# ADC.net
KiCad netlist of a schematic drawn in Altium Designer
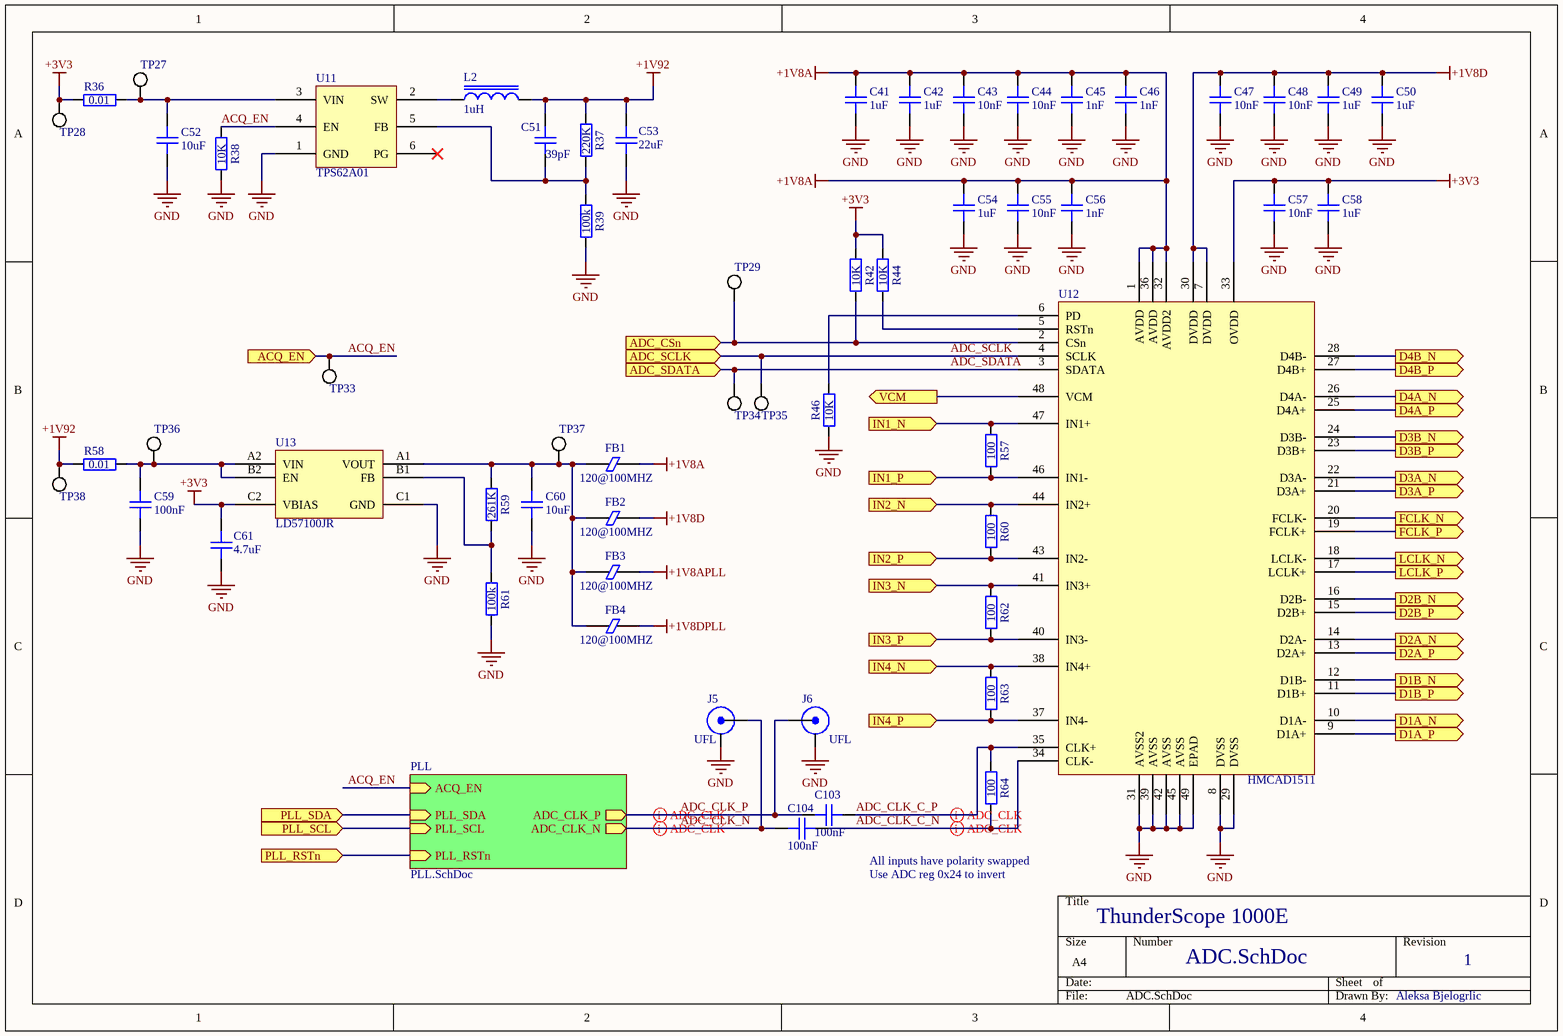
[diagram p0: ADC.SchDoc]

(export (version "E")
  (design (tool "Eeschema 10.0.6"))
  (components
    (comp (ref "C41")
      (value "1uF")
      (footprint "GEN_C_0402")
      (libsource (lib "DSO") (part "CAP 1uF 25V X5R 0402"))
    )
    (comp (ref "C42")
      (value "1uF")
      (footprint "GEN_C_0402")
      (libsource (lib "DSO") (part "CAP 1uF 25V X5R 0402"))
    )
    (comp (ref "C43")
      (value "10nF")
      (footprint "GEN_C_0402")
      (libsource (lib "DSO") (part "CAP 10nF 50V X7R 0402"))
    )
    (comp (ref "C44")
      (value "10nF")
      (footprint "GEN_C_0402")
      (libsource (lib "DSO") (part "CAP 10nF 50V X7R 0402"))
    )
    (comp (ref "C45")
      (value "1nF")
      (footprint "GEN_C_0402")
      (libsource (lib "DSO") (part "CAP 1nF 50V C0G 0402"))
    )
    (comp (ref "C46")
      (value "1nF")
      (footprint "GEN_C_0402")
      (libsource (lib "DSO") (part "CAP 1nF 50V C0G 0402"))
    )
    (comp (ref "C47")
      (value "10nF")
      (footprint "GEN_C_0402")
      (libsource (lib "DSO") (part "CAP 10nF 50V X7R 0402"))
    )
    (comp (ref "C48")
      (value "10nF")
      (footprint "GEN_C_0402")
      (libsource (lib "DSO") (part "CAP 10nF 50V X7R 0402"))
    )
    (comp (ref "C49")
      (value "1uF")
      (footprint "GEN_C_0402")
      (libsource (lib "DSO") (part "CAP 1uF 25V X5R 0402"))
    )
    (comp (ref "C50")
      (value "1uF")
      (footprint "GEN_C_0402")
      (libsource (lib "DSO") (part "CAP 1uF 25V X5R 0402"))
    )
    (comp (ref "C51")
      (value "39pF")
      (footprint "GEN_C_0402")
      (libsource (lib "DSO") (part "CAP 39pF 50V C0G 0402"))
    )
    (comp (ref "C52")
      (value "10uF")
      (footprint "GEN_C_0603")
      (libsource (lib "DSO") (part "CAP 10uF 10V X5R 0603"))
    )
    (comp (ref "C53")
      (value "22uF")
      (footprint "GEN_C_0805")
      (libsource (lib "DSO") (part "CAP 22uF 25V X5R 0805"))
    )
    (comp (ref "C54")
      (value "1uF")
      (footprint "GEN_C_0402")
      (libsource (lib "DSO") (part "CAP 1uF 25V X5R 0402"))
    )
    (comp (ref "C55")
      (value "10nF")
      (footprint "GEN_C_0402")
      (libsource (lib "DSO") (part "CAP 10nF 50V X7R 0402"))
    )
    (comp (ref "C56")
      (value "1nF")
      (footprint "GEN_C_0402")
      (libsource (lib "DSO") (part "CAP 1nF 50V C0G 0402"))
    )
    (comp (ref "C57")
      (value "10nF")
      (footprint "GEN_C_0402")
      (libsource (lib "DSO") (part "CAP 10nF 50V X7R 0402"))
    )
    (comp (ref "C58")
      (value "1uF")
      (footprint "GEN_C_0402")
      (libsource (lib "DSO") (part "CAP 1uF 25V X5R 0402"))
    )
    (comp (ref "C59")
      (value "100nF")
      (footprint "GEN_C_0402")
      (libsource (lib "DSO") (part "CAP 100nF 16V X7R 0402"))
    )
    (comp (ref "C60")
      (value "10uF")
      (footprint "GEN_C_0603")
      (libsource (lib "DSO") (part "CAP 10uF 10V X5R 0603"))
    )
    (comp (ref "C61")
      (value "4.7uF")
      (footprint "GEN_C_0402")
      (libsource (lib "DSO") (part "CAP 4.7uF 6.3V X5R 0402"))
    )
    (comp (ref "C103")
      (value "100nF")
      (footprint "GEN_C_0402")
      (libsource (lib "DSO") (part "CAP 100nF 16V X7R 0402"))
    )
    (comp (ref "C104")
      (value "100nF")
      (footprint "GEN_C_0402")
      (libsource (lib "DSO") (part "CAP 100nF 16V X7R 0402"))
    )
    (comp (ref "FB1")
      (value "120@100MHZ")
      (footprint "GEN_R_0402")
      (libsource (lib "DSO") (part "FERRITE BEAD 120 OHM 0402"))
    )
    (comp (ref "FB2")
      (value "120@100MHZ")
      (footprint "GEN_R_0402")
      (libsource (lib "DSO") (part "FERRITE BEAD 120 OHM 0402"))
    )
    (comp (ref "FB3")
      (value "120@100MHZ")
      (footprint "GEN_R_0402")
      (libsource (lib "DSO") (part "FERRITE BEAD 120 OHM 0402"))
    )
    (comp (ref "FB4")
      (value "120@100MHZ")
      (footprint "GEN_R_0402")
      (libsource (lib "DSO") (part "FERRITE BEAD 120 OHM 0402"))
    )
    (comp (ref "J5") (value "UFL") (footprint "TE_2334884-1") (libsource (lib "DSO") (part "UFL Jack SMD")))
    (comp (ref "J6") (value "UFL") (footprint "TE_2334884-1") (libsource (lib "DSO") (part "UFL Jack SMD")))
    (comp (ref "L2")
      (value "1uH")
      (footprint "GEN_L_1210")
      (libsource (lib "DSO") (part "IND 1uH 3.1A 45 MOHM 1210"))
    )
    (comp (ref "R36")
      (value "0.01")
      (footprint "GEN_R_0603")
      (fields (field (name "TOLERANCE") "1%"))
      (libsource (lib "DSO") (part "RES 0.01 OHM 1% 1/4W 0603"))
    )
    (comp (ref "R37")
      (value "220K")
      (footprint "GEN_R_0402")
      (fields (field (name "TOLERANCE") "1%"))
      (libsource (lib "DSO") (part "RES 220K OHM 1% 1/16W 0402"))
    )
    (comp (ref "R38")
      (value "10K")
      (footprint "GEN_R_0402")
      (fields (field (name "TOLERANCE") "1%"))
      (libsource (lib "DSO") (part "RES 10K OHM 1% 1/10W 0402"))
    )
    (comp (ref "R39")
      (value "100k")
      (footprint "GEN_R_0402")
      (fields (field (name "TOLERANCE") "1%"))
      (libsource (lib "DSO") (part "RES 100K OHM 1% 1/10W 0402"))
    )
    (comp (ref "R42")
      (value "10K")
      (footprint "GEN_R_0402")
      (fields (field (name "TOLERANCE") "1%"))
      (libsource (lib "DSO") (part "RES 10K OHM 1% 1/10W 0402"))
    )
    (comp (ref "R44")
      (value "10K")
      (footprint "GEN_R_0402")
      (fields (field (name "TOLERANCE") "1%"))
      (libsource (lib "DSO") (part "RES 10K OHM 1% 1/10W 0402"))
    )
    (comp (ref "R46")
      (value "10K")
      (footprint "GEN_R_0402")
      (fields (field (name "TOLERANCE") "1%"))
      (libsource (lib "") (part "RES 10K OHM 1% 1/10W 0402_1"))
    )
    (comp (ref "R57")
      (value "100")
      (footprint "GEN_R_0402")
      (fields (field (name "TOLERANCE") "1%"))
      (libsource (lib "DSO") (part "RES 100 OHM 1% 1/10W 0402"))
    )
    (comp (ref "R58")
      (value "0.01")
      (footprint "GEN_R_0603")
      (fields (field (name "TOLERANCE") "1%"))
      (libsource (lib "DSO") (part "RES 0.01 OHM 1% 1/4W 0603"))
    )
    (comp (ref "R59")
      (value "261K")
      (footprint "GEN_R_0402")
      (fields (field (name "TOLERANCE") "1%"))
      (libsource (lib "DSO") (part "RES 261K OHM 1% 1/16W 0402"))
    )
    (comp (ref "R60")
      (value "100")
      (footprint "GEN_R_0402")
      (fields (field (name "TOLERANCE") "1%"))
      (libsource (lib "DSO") (part "RES 100 OHM 1% 1/10W 0402"))
    )
    (comp (ref "R61")
      (value "100k")
      (footprint "GEN_R_0402")
      (fields (field (name "TOLERANCE") "1%"))
      (libsource (lib "DSO") (part "RES 100K OHM 1% 1/10W 0402"))
    )
    (comp (ref "R62")
      (value "100")
      (footprint "GEN_R_0402")
      (fields (field (name "TOLERANCE") "1%"))
      (libsource (lib "DSO") (part "RES 100 OHM 1% 1/10W 0402"))
    )
    (comp (ref "R63")
      (value "100")
      (footprint "GEN_R_0402")
      (fields (field (name "TOLERANCE") "1%"))
      (libsource (lib "DSO") (part "RES 100 OHM 1% 1/10W 0402"))
    )
    (comp (ref "R64")
      (value "100")
      (footprint "GEN_R_0402")
      (fields (field (name "TOLERANCE") "1%"))
      (libsource (lib "DSO") (part "RES 100 OHM 1% 1/10W 0402"))
    )
    (comp (ref "TP27") (value "PCB") (footprint "GEN_TP_PCB") (libsource (lib "DSO") (part "TP PCB 1mm")))
    (comp (ref "TP28") (value "PCB") (footprint "GEN_TP_PCB") (libsource (lib "DSO") (part "TP PCB 1mm")))
    (comp (ref "TP29") (value "PCB") (footprint "GEN_TP_PCB") (libsource (lib "DSO") (part "TP PCB 1mm")))
    (comp (ref "TP33") (value "PCB") (footprint "GEN_TP_PCB") (libsource (lib "DSO") (part "TP PCB 1mm")))
    (comp (ref "TP34") (value "PCB") (footprint "GEN_TP_PCB") (libsource (lib "DSO") (part "TP PCB 1mm")))
    (comp (ref "TP35") (value "PCB") (footprint "GEN_TP_PCB") (libsource (lib "DSO") (part "TP PCB 1mm")))
    (comp (ref "TP36") (value "PCB") (footprint "GEN_TP_PCB") (libsource (lib "DSO") (part "TP PCB 1mm")))
    (comp (ref "TP37") (value "PCB") (footprint "GEN_TP_PCB") (libsource (lib "DSO") (part "TP PCB 1mm")))
    (comp (ref "TP38") (value "PCB") (footprint "GEN_TP_PCB") (libsource (lib "DSO") (part "TP PCB 1mm")))
    (comp (ref "U11")
      (value "TPS62A01")
      (footprint "TI_SOT563_DRL0006A")
      (libsource (lib "DSO") (part "IC BUCK TPS62A01"))
    )
    (comp (ref "U12")
      (value "HMCAD1511")
      (footprint "AD_QFN48_LP7")
      (libsource (lib "DSO") (part "IC ADC HMCAD1511"))
    )
    (comp (ref "U13")
      (value "LD57100JR")
      (footprint "ST_FlipChip6")
      (libsource (lib "DSO") (part "IC LDO LD57100JR"))
    )
  )
  (nets
    (net (code "1") (name "+1V8A") (class "Default")
      (node (ref "C41") (pin "2") (pinfunction "2_2") (pintype "passive"))
      (node (ref "C42") (pin "2") (pinfunction "2_2") (pintype "passive"))
      (node (ref "C43") (pin "2") (pinfunction "2_2") (pintype "passive"))
      (node (ref "C44") (pin "2") (pinfunction "2_2") (pintype "passive"))
      (node (ref "C45") (pin "2") (pinfunction "2_2") (pintype "passive"))
      (node (ref "C46") (pin "2") (pinfunction "2_2") (pintype "passive"))
      (node (ref "C54") (pin "2") (pinfunction "2_2") (pintype "passive"))
      (node (ref "C55") (pin "2") (pinfunction "2_2") (pintype "passive"))
      (node (ref "C56") (pin "2") (pinfunction "2_2") (pintype "passive"))
      (node (ref "FB1") (pin "2") (pinfunction "2_2") (pintype "passive"))
      (node (ref "U12") (pin "1") (pinfunction "AVDD_1") (pintype "passive"))
      (node (ref "U12") (pin "32") (pinfunction "AVDD2_32") (pintype "passive"))
      (node (ref "U12") (pin "36") (pinfunction "AVDD_36") (pintype "passive"))
    )
    (net (code "2") (name "+1V8APLL") (class "Default")
      (node (ref "FB3") (pin "2") (pinfunction "2_2") (pintype "passive"))
    )
    (net (code "3") (name "+1V8D") (class "Default")
      (node (ref "C47") (pin "2") (pinfunction "2_2") (pintype "passive"))
      (node (ref "C48") (pin "2") (pinfunction "2_2") (pintype "passive"))
      (node (ref "C49") (pin "2") (pinfunction "2_2") (pintype "passive"))
      (node (ref "C50") (pin "2") (pinfunction "2_2") (pintype "passive"))
      (node (ref "FB2") (pin "2") (pinfunction "2_2") (pintype "passive"))
      (node (ref "U12") (pin "30") (pinfunction "DVDD_30") (pintype "passive"))
      (node (ref "U12") (pin "7") (pinfunction "DVDD_7") (pintype "passive"))
    )
    (net (code "4") (name "+1V8DPLL") (class "Default")
      (node (ref "FB4") (pin "2") (pinfunction "2_2") (pintype "passive"))
    )
    (net (code "5") (name "+1V92") (class "Default")
      (node (ref "C51") (pin "2") (pinfunction "2_2") (pintype "passive"))
      (node (ref "C53") (pin "2") (pinfunction "2_2") (pintype "passive"))
      (node (ref "L2") (pin "2") (pinfunction "2_2") (pintype "passive"))
      (node (ref "R37") (pin "2") (pinfunction "2_2") (pintype "passive"))
      (node (ref "R58") (pin "1") (pinfunction "1_1") (pintype "passive"))
      (node (ref "TP38") (pin "1") (pinfunction "1_1") (pintype "passive"))
    )
    (net (code "6") (name "+3V3") (class "Default")
      (node (ref "C57") (pin "2") (pinfunction "2_2") (pintype "passive"))
      (node (ref "C58") (pin "2") (pinfunction "2_2") (pintype "passive"))
      (node (ref "C61") (pin "2") (pinfunction "2_2") (pintype "passive"))
      (node (ref "R36") (pin "1") (pinfunction "1_1") (pintype "passive"))
      (node (ref "R42") (pin "2") (pinfunction "2_2") (pintype "passive"))
      (node (ref "R44") (pin "2") (pinfunction "2_2") (pintype "passive"))
      (node (ref "TP28") (pin "1") (pinfunction "1_1") (pintype "passive"))
      (node (ref "U12") (pin "33") (pinfunction "OVDD_33") (pintype "passive"))
      (node (ref "U13") (pin "C2") (pinfunction "VBIAS_C2") (pintype "passive"))
    )
    (net (code "7") (name "/ACQ_EN") (class "Default")
      (node (ref "R38") (pin "2") (pinfunction "2_2") (pintype "passive"))
      (node (ref "TP33") (pin "1") (pinfunction "1_1") (pintype "passive"))
      (node (ref "U11") (pin "4") (pinfunction "EN_4") (pintype "passive"))
    )
    (net (code "8") (name "/ADC_CLK_C_N") (class "Default")
      (node (ref "C104") (pin "1") (pinfunction "1_1") (pintype "passive"))
      (node (ref "R64") (pin "1") (pinfunction "1_1") (pintype "passive"))
      (node (ref "U12") (pin "34") (pinfunction "CLK-_34") (pintype "passive"))
    )
    (net (code "9") (name "/ADC_CLK_C_P") (class "Default")
      (node (ref "C103") (pin "1") (pinfunction "1_1") (pintype "passive"))
      (node (ref "R64") (pin "2") (pinfunction "2_2") (pintype "passive"))
      (node (ref "U12") (pin "35") (pinfunction "CLK+_35") (pintype "passive"))
    )
    (net (code "10") (name "/ADC_CLK_N") (class "Default")
      (node (ref "C104") (pin "2") (pinfunction "2_2") (pintype "passive"))
      (node (ref "J5") (pin "1") (pinfunction "Signal_1") (pintype "passive"))
    )
    (net (code "11") (name "/ADC_CLK_P") (class "Default")
      (node (ref "C103") (pin "2") (pinfunction "2_2") (pintype "passive"))
      (node (ref "J6") (pin "1") (pinfunction "Signal_1") (pintype "passive"))
    )
    (net (code "12") (name "/ADC_CSn") (class "Default")
      (node (ref "R42") (pin "1") (pinfunction "1_1") (pintype "passive"))
      (node (ref "TP29") (pin "1") (pinfunction "1_1") (pintype "passive"))
      (node (ref "U12") (pin "2") (pinfunction "CSn_2") (pintype "passive"))
    )
    (net (code "13") (name "/ADC_SCLK") (class "Default")
      (node (ref "TP35") (pin "1") (pinfunction "1_1") (pintype "passive"))
      (node (ref "U12") (pin "4") (pinfunction "SCLK_4") (pintype "passive"))
    )
    (net (code "14") (name "/ADC_SDATA") (class "Default")
      (node (ref "TP34") (pin "1") (pinfunction "1_1") (pintype "passive"))
      (node (ref "U12") (pin "3") (pinfunction "SDATA_3") (pintype "passive"))
    )
    (net (code "15") (name "/D1A_N") (class "Default")
      (node (ref "U12") (pin "10") (pinfunction "D1A-_10") (pintype "passive"))
    )
    (net (code "16") (name "/D1A_P") (class "Default")
      (node (ref "U12") (pin "9") (pinfunction "D1A+_9") (pintype "passive"))
    )
    (net (code "17") (name "/D1B_N") (class "Default")
      (node (ref "U12") (pin "12") (pinfunction "D1B-_12") (pintype "passive"))
    )
    (net (code "18") (name "/D1B_P") (class "Default")
      (node (ref "U12") (pin "11") (pinfunction "D1B+_11") (pintype "passive"))
    )
    (net (code "19") (name "/D2A_N") (class "Default")
      (node (ref "U12") (pin "14") (pinfunction "D2A-_14") (pintype "passive"))
    )
    (net (code "20") (name "/D2A_P") (class "Default")
      (node (ref "U12") (pin "13") (pinfunction "D2A+_13") (pintype "passive"))
    )
    (net (code "21") (name "/D2B_N") (class "Default")
      (node (ref "U12") (pin "16") (pinfunction "D2B-_16") (pintype "passive"))
    )
    (net (code "22") (name "/D2B_P") (class "Default")
      (node (ref "U12") (pin "15") (pinfunction "D2B+_15") (pintype "passive"))
    )
    (net (code "23") (name "/D3A_N") (class "Default")
      (node (ref "U12") (pin "22") (pinfunction "D3A-_22") (pintype "passive"))
    )
    (net (code "24") (name "/D3A_P") (class "Default")
      (node (ref "U12") (pin "21") (pinfunction "D3A+_21") (pintype "passive"))
    )
    (net (code "25") (name "/D3B_N") (class "Default")
      (node (ref "U12") (pin "24") (pinfunction "D3B-_24") (pintype "passive"))
    )
    (net (code "26") (name "/D3B_P") (class "Default")
      (node (ref "U12") (pin "23") (pinfunction "D3B+_23") (pintype "passive"))
    )
    (net (code "27") (name "/D4A_N") (class "Default")
      (node (ref "U12") (pin "26") (pinfunction "D4A-_26") (pintype "passive"))
    )
    (net (code "28") (name "/D4A_P") (class "Default")
      (node (ref "U12") (pin "25") (pinfunction "D4A+_25") (pintype "passive"))
    )
    (net (code "29") (name "/D4B_N") (class "Default")
      (node (ref "U12") (pin "28") (pinfunction "D4B-_28") (pintype "passive"))
    )
    (net (code "30") (name "/D4B_P") (class "Default")
      (node (ref "U12") (pin "27") (pinfunction "D4B+_27") (pintype "passive"))
    )
    (net (code "31") (name "/FCLK_N") (class "Default")
      (node (ref "U12") (pin "20") (pinfunction "FCLK-_20") (pintype "passive"))
    )
    (net (code "32") (name "/FCLK_P") (class "Default")
      (node (ref "U12") (pin "19") (pinfunction "FCLK+_19") (pintype "passive"))
    )
    (net (code "33") (name "/IN1_N") (class "Default")
      (node (ref "R57") (pin "2") (pinfunction "2_2") (pintype "passive"))
      (node (ref "U12") (pin "47") (pinfunction "IN1+_47") (pintype "passive"))
    )
    (net (code "34") (name "/IN1_P") (class "Default")
      (node (ref "R57") (pin "1") (pinfunction "1_1") (pintype "passive"))
      (node (ref "U12") (pin "46") (pinfunction "IN1-_46") (pintype "passive"))
    )
    (net (code "35") (name "/IN2_N") (class "Default")
      (node (ref "R60") (pin "2") (pinfunction "2_2") (pintype "passive"))
      (node (ref "U12") (pin "44") (pinfunction "IN2+_44") (pintype "passive"))
    )
    (net (code "36") (name "/IN2_P") (class "Default")
      (node (ref "R60") (pin "1") (pinfunction "1_1") (pintype "passive"))
      (node (ref "U12") (pin "43") (pinfunction "IN2-_43") (pintype "passive"))
    )
    (net (code "37") (name "/IN3_N") (class "Default")
      (node (ref "R62") (pin "2") (pinfunction "2_2") (pintype "passive"))
      (node (ref "U12") (pin "41") (pinfunction "IN3+_41") (pintype "passive"))
    )
    (net (code "38") (name "/IN3_P") (class "Default")
      (node (ref "R62") (pin "1") (pinfunction "1_1") (pintype "passive"))
      (node (ref "U12") (pin "40") (pinfunction "IN3-_40") (pintype "passive"))
    )
    (net (code "39") (name "/IN4_N") (class "Default")
      (node (ref "R63") (pin "2") (pinfunction "2_2") (pintype "passive"))
      (node (ref "U12") (pin "38") (pinfunction "IN4+_38") (pintype "passive"))
    )
    (net (code "40") (name "/IN4_P") (class "Default")
      (node (ref "R63") (pin "1") (pinfunction "1_1") (pintype "passive"))
      (node (ref "U12") (pin "37") (pinfunction "IN4-_37") (pintype "passive"))
    )
    (net (code "41") (name "/LCLK_N") (class "Default")
      (node (ref "U12") (pin "18") (pinfunction "LCLK-_18") (pintype "passive"))
    )
    (net (code "42") (name "/LCLK_P") (class "Default")
      (node (ref "U12") (pin "17") (pinfunction "LCLK+_17") (pintype "passive"))
    )
    (net (code "46") (name "/VCM") (class "Default")
      (node (ref "U12") (pin "48") (pinfunction "VCM_48") (pintype "passive"))
    )
    (net (code "47") (name "GND") (class "Default")
      (node (ref "C41") (pin "1") (pinfunction "1_1") (pintype "passive"))
      (node (ref "C42") (pin "1") (pinfunction "1_1") (pintype "passive"))
      (node (ref "C43") (pin "1") (pinfunction "1_1") (pintype "passive"))
      (node (ref "C44") (pin "1") (pinfunction "1_1") (pintype "passive"))
      (node (ref "C45") (pin "1") (pinfunction "1_1") (pintype "passive"))
      (node (ref "C46") (pin "1") (pinfunction "1_1") (pintype "passive"))
      (node (ref "C47") (pin "1") (pinfunction "1_1") (pintype "passive"))
      (node (ref "C48") (pin "1") (pinfunction "1_1") (pintype "passive"))
      (node (ref "C49") (pin "1") (pinfunction "1_1") (pintype "passive"))
      (node (ref "C50") (pin "1") (pinfunction "1_1") (pintype "passive"))
      (node (ref "C52") (pin "1") (pinfunction "1_1") (pintype "passive"))
      (node (ref "C53") (pin "1") (pinfunction "1_1") (pintype "passive"))
      (node (ref "C54") (pin "1") (pinfunction "1_1") (pintype "passive"))
      (node (ref "C55") (pin "1") (pinfunction "1_1") (pintype "passive"))
      (node (ref "C56") (pin "1") (pinfunction "1_1") (pintype "passive"))
      (node (ref "C57") (pin "1") (pinfunction "1_1") (pintype "passive"))
      (node (ref "C58") (pin "1") (pinfunction "1_1") (pintype "passive"))
      (node (ref "C59") (pin "1") (pinfunction "1_1") (pintype "passive"))
      (node (ref "C60") (pin "1") (pinfunction "1_1") (pintype "passive"))
      (node (ref "C61") (pin "1") (pinfunction "1_1") (pintype "passive"))
      (node (ref "J5") (pin "2") (pinfunction "SHIELD_2") (pintype "passive"))
      (node (ref "J6") (pin "2") (pinfunction "SHIELD_2") (pintype "passive"))
      (node (ref "R38") (pin "1") (pinfunction "1_1") (pintype "passive"))
      (node (ref "R39") (pin "1") (pinfunction "1_1") (pintype "passive"))
      (node (ref "R46") (pin "2") (pinfunction "2_2") (pintype "passive"))
      (node (ref "R61") (pin "1") (pinfunction "1_1") (pintype "passive"))
      (node (ref "U11") (pin "1") (pinfunction "GND_1") (pintype "power_in"))
      (node (ref "U12") (pin "29") (pinfunction "DVSS_29") (pintype "passive"))
      (node (ref "U12") (pin "31") (pinfunction "AVSS2_31") (pintype "passive"))
      (node (ref "U12") (pin "39") (pinfunction "AVSS_39") (pintype "passive"))
      (node (ref "U12") (pin "42") (pinfunction "AVSS_42") (pintype "passive"))
      (node (ref "U12") (pin "45") (pinfunction "AVSS_45") (pintype "passive"))
      (node (ref "U12") (pin "49") (pinfunction "EPAD_49") (pintype "passive"))
      (node (ref "U12") (pin "8") (pinfunction "DVSS_8") (pintype "passive"))
      (node (ref "U13") (pin "C1") (pinfunction "GND_C1") (pintype "passive"))
    )
    (net (code "48") (name "Net-(U11-FB)") (class "Default")
      (node (ref "C51") (pin "1") (pinfunction "1_1") (pintype "passive"))
      (node (ref "R37") (pin "1") (pinfunction "1_1") (pintype "passive"))
      (node (ref "R39") (pin "2") (pinfunction "2_2") (pintype "passive"))
      (node (ref "U11") (pin "5") (pinfunction "FB_5") (pintype "passive"))
    )
    (net (code "49") (name "Net-(U11-SW)") (class "Default")
      (node (ref "L2") (pin "1") (pinfunction "1_1") (pintype "passive"))
      (node (ref "U11") (pin "2") (pinfunction "SW_2") (pintype "passive"))
    )
    (net (code "50") (name "Net-(U11-VIN)") (class "Default")
      (node (ref "C52") (pin "2") (pinfunction "2_2") (pintype "passive"))
      (node (ref "R36") (pin "2") (pinfunction "2_2") (pintype "passive"))
      (node (ref "TP27") (pin "1") (pinfunction "1_1") (pintype "passive"))
      (node (ref "U11") (pin "3") (pinfunction "VIN_3") (pintype "power_in"))
    )
    (net (code "51") (name "Net-(U12-PD)") (class "Default")
      (node (ref "R46") (pin "1") (pinfunction "1_1") (pintype "passive"))
      (node (ref "U12") (pin "6") (pinfunction "PD_6") (pintype "passive"))
    )
    (net (code "52") (name "Net-(U12-RSTn)") (class "Default")
      (node (ref "R44") (pin "1") (pinfunction "1_1") (pintype "passive"))
      (node (ref "U12") (pin "5") (pinfunction "RSTn_5") (pintype "passive"))
    )
    (net (code "53") (name "Net-(U13-EN)") (class "Default")
      (node (ref "C59") (pin "2") (pinfunction "2_2") (pintype "passive"))
      (node (ref "R58") (pin "2") (pinfunction "2_2") (pintype "passive"))
      (node (ref "TP36") (pin "1") (pinfunction "1_1") (pintype "passive"))
      (node (ref "U13") (pin "A2") (pinfunction "VIN_A2") (pintype "passive"))
      (node (ref "U13") (pin "B2") (pinfunction "EN_B2") (pintype "passive"))
    )
    (net (code "54") (name "Net-(U13-FB)") (class "Default")
      (node (ref "R59") (pin "1") (pinfunction "1_1") (pintype "passive"))
      (node (ref "R61") (pin "2") (pinfunction "2_2") (pintype "passive"))
      (node (ref "U13") (pin "B1") (pinfunction "FB_B1") (pintype "passive"))
    )
    (net (code "55") (name "Net-(U13-VOUT)") (class "Default")
      (node (ref "C60") (pin "2") (pinfunction "2_2") (pintype "passive"))
      (node (ref "FB1") (pin "1") (pinfunction "1_1") (pintype "passive"))
      (node (ref "FB2") (pin "1") (pinfunction "1_1") (pintype "passive"))
      (node (ref "FB3") (pin "1") (pinfunction "1_1") (pintype "passive"))
      (node (ref "FB4") (pin "1") (pinfunction "1_1") (pintype "passive"))
      (node (ref "R59") (pin "2") (pinfunction "2_2") (pintype "passive"))
      (node (ref "TP37") (pin "1") (pinfunction "1_1") (pintype "passive"))
      (node (ref "U13") (pin "A1") (pinfunction "VOUT_A1") (pintype "passive"))
    )
    (net (code "56") (name "unconnected-(U11-PG-Pad6)") (class "Default")
      (node (ref "U11") (pin "6") (pinfunction "PG_6") (pintype "passive+no_connect"))
    )
  )
)
